# TE0706.net
KiCad netlist of a schematic drawn in Altium Designer
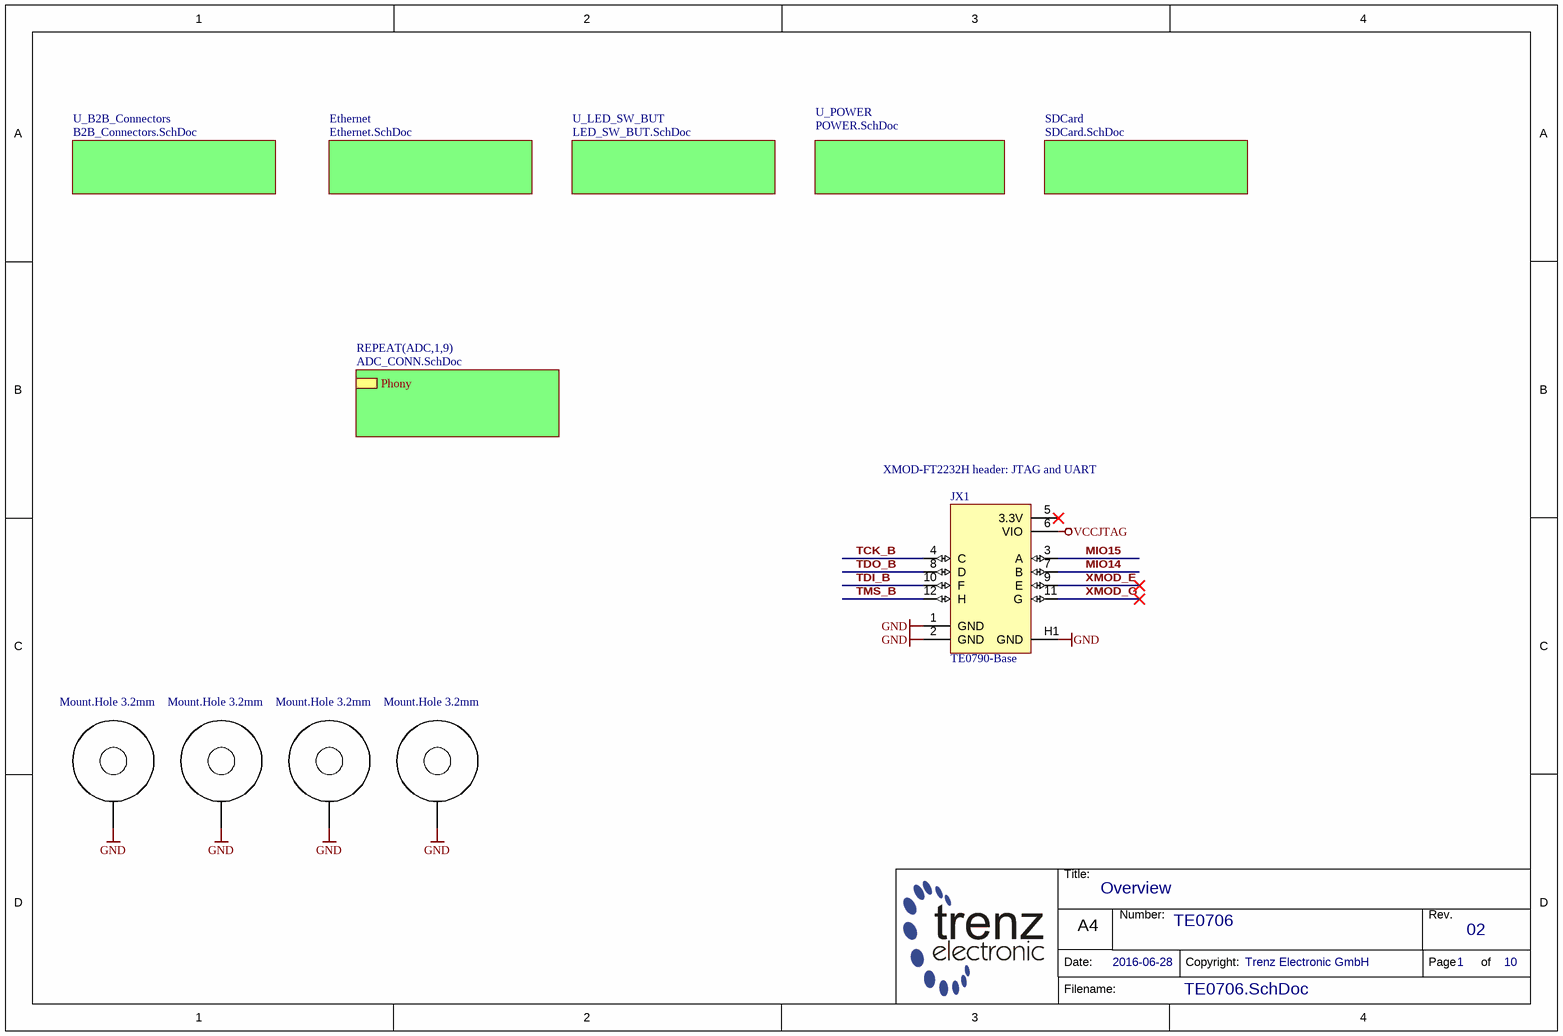
[diagram p0: TE0706.SchDoc]

(export (version "E")
  (design (tool "Eeschema 10.0.6"))
  (components
    (comp (ref "H1")
      (value "Mount.Hole 3.2mm")
      (footprint "MHole3_2mm")
      (libsource (lib "TE") (part "MHole"))
    )
    (comp (ref "H2")
      (value "Mount.Hole 3.2mm")
      (footprint "MHole3_2mm")
      (libsource (lib "TE") (part "MHole"))
    )
    (comp (ref "H3")
      (value "Mount.Hole 3.2mm")
      (footprint "MHole3_2mm")
      (libsource (lib "TE") (part "MHole"))
    )
    (comp (ref "H4")
      (value "Mount.Hole 3.2mm")
      (footprint "MHole3_2mm")
      (libsource (lib "TE") (part "MHole"))
    )
    (comp (ref "JX1")
      (value "TE0790-Base")
      (footprint "TE0790-Base")
      (libsource (lib "TE") (part "TE0790-JB"))
    )
  )
  (nets
    (net (code "1") (name "/MIO14") (class "Default")
      (node (ref "JX1") (pin "7") (pinfunction "B_7") (pintype "bidirectional"))
    )
    (net (code "2") (name "/MIO15") (class "Default")
      (node (ref "JX1") (pin "3") (pinfunction "A_3") (pintype "bidirectional"))
    )
    (net (code "4") (name "/TCK_B") (class "Default")
      (node (ref "JX1") (pin "4") (pinfunction "C_4") (pintype "bidirectional"))
    )
    (net (code "5") (name "/TDI_B") (class "Default")
      (node (ref "JX1") (pin "10") (pinfunction "F_10") (pintype "bidirectional"))
    )
    (net (code "6") (name "/TDO_B") (class "Default")
      (node (ref "JX1") (pin "8") (pinfunction "D_8") (pintype "bidirectional"))
    )
    (net (code "7") (name "/TMS_B") (class "Default")
      (node (ref "JX1") (pin "12") (pinfunction "H_12") (pintype "bidirectional"))
    )
    (net (code "8") (name "/XMOD_E") (class "Default")
      (node (ref "JX1") (pin "9") (pinfunction "E_9") (pintype "bidirectional+no_connect"))
    )
    (net (code "9") (name "/XMOD_G") (class "Default")
      (node (ref "JX1") (pin "11") (pinfunction "G_11") (pintype "bidirectional+no_connect"))
    )
    (net (code "10") (name "GND") (class "Default")
      (node (ref "H1") (pin "1") (pinfunction "1_1") (pintype "passive"))
      (node (ref "H2") (pin "1") (pinfunction "1_1") (pintype "passive"))
      (node (ref "H3") (pin "1") (pinfunction "1_1") (pintype "passive"))
      (node (ref "H4") (pin "1") (pinfunction "1_1") (pintype "passive"))
      (node (ref "JX1") (pin "1") (pinfunction "GND_1") (pintype "power_in"))
      (node (ref "JX1") (pin "2") (pinfunction "GND_2") (pintype "power_in"))
      (node (ref "JX1") (pin "H1") (pinfunction "GND_H1") (pintype "power_in"))
    )
    (net (code "11") (name "VCCJTAG") (class "Default")
      (node (ref "JX1") (pin "6") (pinfunction "VIO_6") (pintype "power_in"))
    )
    (net (code "12") (name "unconnected-(JX1-3.3V-Pad5)") (class "Default")
      (node (ref "JX1") (pin "5") (pinfunction "3.3V_5") (pintype "power_in+no_connect"))
    )
  )
)
